# Sheet2.net
KiCad netlist of a schematic drawn in Altium Designer
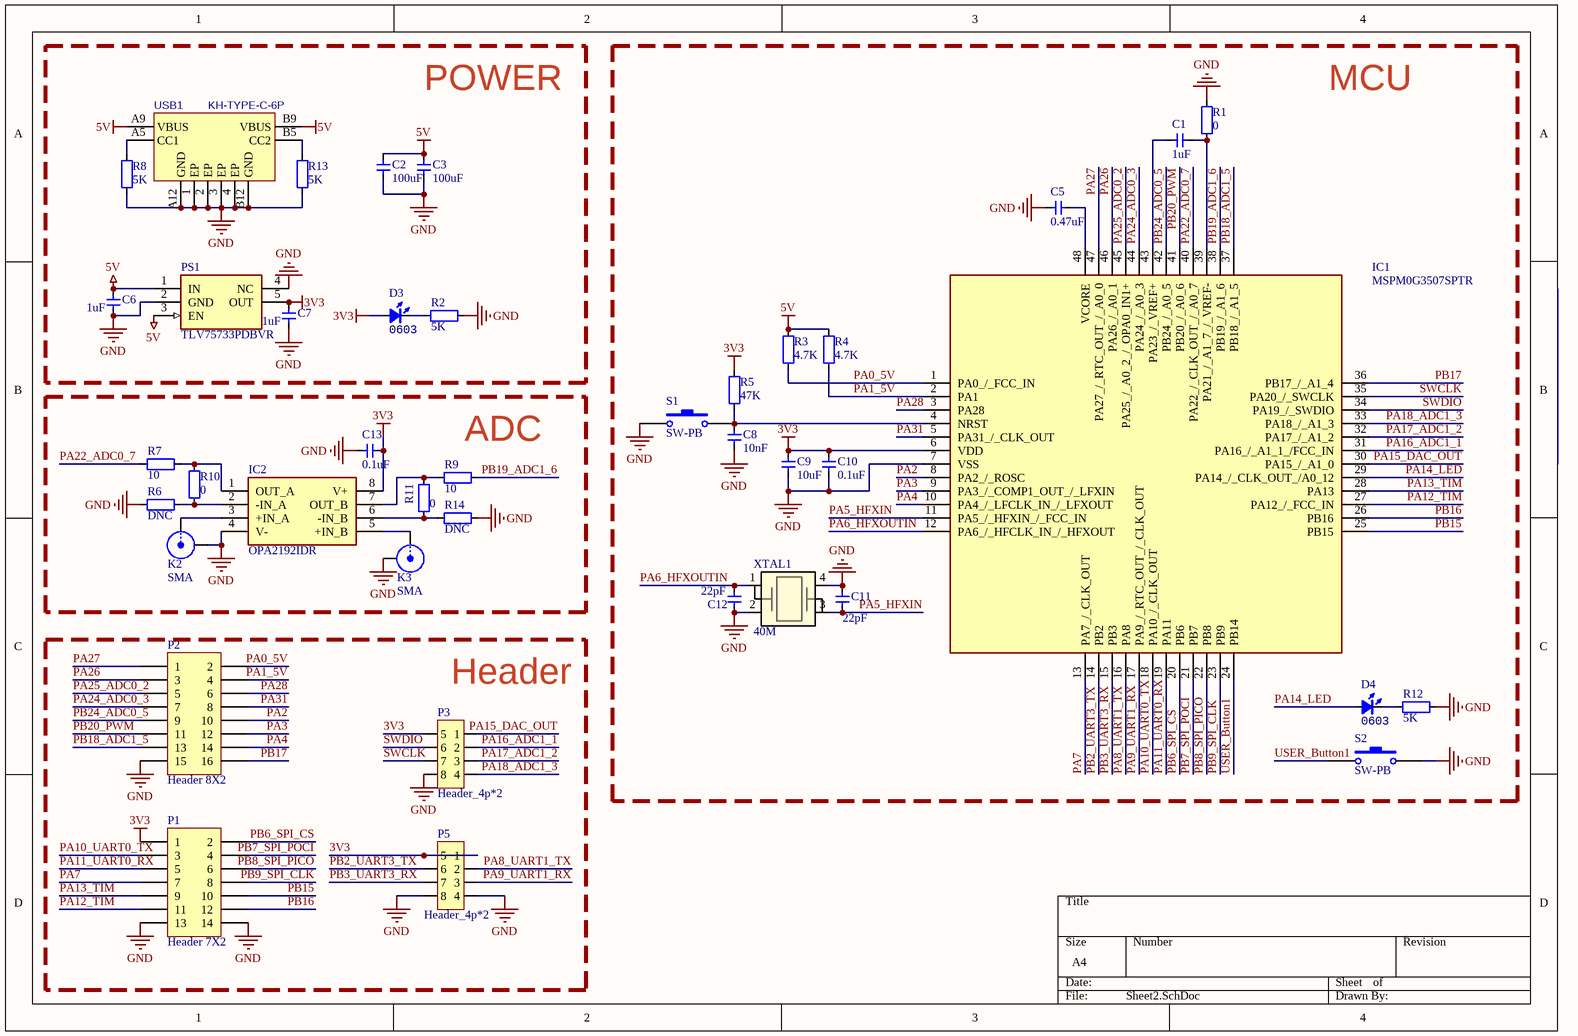
[diagram p0: Sheet2.SchDoc]

(export (version "E")
  (design (tool "Eeschema 10.0.6"))
  (components
    (comp (ref "C1")
      (value "1uF")
      (footprint "CAP_0402")
      (description "Capacitor")
      (libsource (lib "MoonFall") (part "电容-0402"))
    )
    (comp (ref "C2")
      (value "100uF")
      (footprint "1206-CAP")
      (description "Capacitor")
      (libsource (lib "MyPcbLib") (part "电容-1206"))
    )
    (comp (ref "C3")
      (value "100uF")
      (footprint "1206-CAP")
      (description "Capacitor")
      (libsource (lib "MyPcbLib") (part "电容-1206"))
    )
    (comp (ref "C5")
      (value "0.47uF")
      (footprint "CAP_0402")
      (description "Capacitor")
      (libsource (lib "MoonFall") (part "电容-0402"))
    )
    (comp (ref "C6")
      (value "1uF")
      (footprint "CAP_0402")
      (description "Capacitor")
      (libsource (lib "MoonFall") (part "电容-0402"))
    )
    (comp (ref "C7")
      (value "1uF")
      (footprint "CAP_0402")
      (description "Capacitor")
      (libsource (lib "MoonFall") (part "电容-0402"))
    )
    (comp (ref "C8")
      (value "10nF")
      (footprint "CAP_0402")
      (description "Capacitor")
      (libsource (lib "MyPcbLib") (part "电容-0402"))
    )
    (comp (ref "C9")
      (value "10uF")
      (footprint "CAP_0402")
      (description "Capacitor")
      (libsource (lib "MoonFall") (part "电容-0402"))
    )
    (comp (ref "C10")
      (value "0.1uF")
      (footprint "CAP_0402")
      (description "Capacitor")
      (libsource (lib "MoonFall") (part "电容-0402"))
    )
    (comp (ref "C11")
      (value "22pF")
      (footprint "CAP_0402")
      (description "Capacitor")
      (libsource (lib "MoonFall") (part "电容-0402"))
    )
    (comp (ref "C12")
      (value "22pF")
      (footprint "CAP_0402")
      (description "Capacitor")
      (libsource (lib "MoonFall") (part "电容-0402"))
    )
    (comp (ref "C13")
      (value "0.1uF")
      (footprint "CAP_0402")
      (description "Capacitor")
      (libsource (lib "MoonFall") (part "电容-0402"))
    )
    (comp (ref "D3")
      (value "3.3V")
      (footprint "0603_led")
      (description "LED")
      (fields (field (name "TYPE") "0603"))
      (libsource (lib "MoonFall") (part "LED_0603"))
    )
    (comp (ref "D4")
      (value "3.3V")
      (footprint "0603_led")
      (description "LED")
      (fields (field (name "TYPE") "0603"))
      (libsource (lib "MoonFall") (part "LED_0603"))
    )
    (comp (ref "IC1")
      (value "MSPM0G3507SPTR")
      (footprint "QFP50P900X900X160-48N")
      (description "Integrated Circuit")
      (fields (field (name "MANUFACTURER_PART_NUMBER") "MSPM0G3507SDGS28R"))
      (libsource (lib "MoonFall") (part "MSPM0G3507SPTR"))
    )
    (comp (ref "IC2")
      (value "OPA2192IDR")
      (footprint "OPA2192IDR")
      (description "Integrated Circuit")
      (fields (field (name "MANUFACTURER_PART_NUMBER") "OPA2192IDR/BKN"))
      (libsource (lib "MoonFall") (part "OPA2192IDR"))
    )
    (comp (ref "K2") (value "SMA") (footprint "SMA-W") (libsource (lib "MoonFall") (part "SMA")))
    (comp (ref "K3") (value "SMA") (footprint "SMA-W") (libsource (lib "MoonFall") (part "SMA")))
    (comp (ref "P1")
      (value "Header 7X2")
      (footprint "201S2X7")
      (description "Header, 7-Pin, Dual row")
      (fields (field (name "PUBLISHER") "Altium Limited"))
      (libsource (lib "Miscellaneous Connectors") (part "Header 7X2"))
    )
    (comp (ref "P2")
      (value "Header 8X2")
      (footprint "201S2X8")
      (description "Header, 8-Pin, Dual row")
      (fields (field (name "PUBLISHER") "Altium Limited"))
      (libsource (lib "Miscellaneous Connectors") (part "Header 8X2"))
    )
    (comp (ref "P3")
      (value "Header_4p*2")
      (footprint "201R2X4")
      (libsource (lib "MoonFall") (part "Header_4p*2"))
    )
    (comp (ref "P5")
      (value "Header_4p*2")
      (footprint "201S2X4")
      (libsource (lib "MoonFall") (part "Header_4p*2"))
    )
    (comp (ref "PS1")
      (value "TLV75733PDBVR")
      (footprint "SOT95P280X145-5N")
      (description "Power Supply")
      (fields (field (name "MOUSER PART NUMBER") "595-TLV75733PDBVR"))
      (libsource (lib "AD9959") (part "TLV75733PDBVR"))
    )
    (comp (ref "R1")
      (value "0")
      (footprint "RES_0402")
      (description "Resistor")
      (libsource (lib "MyPcbLib") (part "电阻-0402"))
    )
    (comp (ref "R2")
      (value "5K")
      (footprint "RES_0402")
      (description "Resistor")
      (libsource (lib "MyPcbLib") (part "电阻-0402"))
    )
    (comp (ref "R3")
      (value "4.7K")
      (footprint "RES_0402")
      (description "Resistor")
      (libsource (lib "") (part "电阻-0402_1"))
    )
    (comp (ref "R4")
      (value "4.7K")
      (footprint "RES_0402")
      (description "Resistor")
      (libsource (lib "") (part "电阻-0402_1"))
    )
    (comp (ref "R5")
      (value "47K")
      (footprint "RES_0402")
      (description "Resistor")
      (libsource (lib "") (part "电阻-0402_1"))
    )
    (comp (ref "R6")
      (value "DNC")
      (footprint "RES_0402")
      (description "Resistor")
      (libsource (lib "MyPcbLib") (part "电阻-0402"))
    )
    (comp (ref "R7")
      (value "10")
      (footprint "RES_0402")
      (description "Resistor")
      (libsource (lib "") (part "电阻-0402_1"))
    )
    (comp (ref "R8")
      (value "5K")
      (footprint "RES_0402")
      (description "Resistor")
      (libsource (lib "") (part "电阻-0402_2"))
    )
    (comp (ref "R9")
      (value "10")
      (footprint "RES_0402")
      (description "Resistor")
      (libsource (lib "MyPcbLib") (part "电阻-0402"))
    )
    (comp (ref "R10")
      (value "0")
      (footprint "RES_0402")
      (description "Resistor")
      (libsource (lib "") (part "电阻-0402_2"))
    )
    (comp (ref "R11")
      (value "0")
      (footprint "RES_0402")
      (description "Resistor")
      (libsource (lib "MyPcbLib") (part "电阻-0402"))
    )
    (comp (ref "R12")
      (value "5K")
      (footprint "RES_0402")
      (description "Resistor")
      (libsource (lib "MyPcbLib") (part "电阻-0402"))
    )
    (comp (ref "R13")
      (value "5K")
      (footprint "RES_0402")
      (description "Resistor")
      (libsource (lib "") (part "电阻-0402_2"))
    )
    (comp (ref "R14")
      (value "DNC")
      (footprint "RES_0402")
      (description "Resistor")
      (libsource (lib "") (part "电阻-0402_3"))
    )
    (comp (ref "S1")
      (value "SW-PB")
      (footprint "KEY-K2")
      (description "Switch")
      (fields (field (name "PUBLISHER") "Altium Limited"))
      (libsource (lib "Miscellaneous Devices") (part "SW-PB"))
    )
    (comp (ref "S2")
      (value "SW-PB")
      (footprint "KEY-K2")
      (description "Switch")
      (fields (field (name "PUBLISHER") "Altium Limited"))
      (libsource (lib "Miscellaneous Devices") (part "SW-PB"))
    )
    (comp (ref "USB1")
      (value "KH-TYPE-C-6P")
      (footprint "TYPE-C-SMD_TYPE-C-31-M-16")
      (fields (field (name "BOM_SUPPLIER PART") "C709355") (field (name "CONTRIBUTOR") "LCSC"))
      (libsource (lib "MoonFall") (part "TYPE-C-6P"))
    )
    (comp (ref "XTAL1")
      (value "40M")
      (footprint "3225-25M")
      (description "No Description Available")
      (fields
        (field (name "MANUFACTURER_PART_NUMBER") "NX3225GA-16.000M-STD-CRG-2")
        (field (name "COPYRIGHT") "Copyright (C) 2022 Ultra Librarian. All rights reserved.")
      )
      (libsource (lib "3225晶振") (part "NX3225GA-16.000M-STD-CRG-2"))
    )
  )
  (nets
    (net (code "1") (name "/PA0_5V") (class "Default")
      (node (ref "IC1") (pin "1") (pinfunction "PA0_/_FCC_IN_1") (pintype "passive"))
      (node (ref "P2") (pin "2") (pinfunction "2_2") (pintype "passive"))
      (node (ref "R3") (pin "1") (pinfunction "1_1") (pintype "passive"))
    )
    (net (code "2") (name "/PA1_5V") (class "Default")
      (node (ref "IC1") (pin "2") (pinfunction "PA1_2") (pintype "passive"))
      (node (ref "P2") (pin "4") (pinfunction "4_4") (pintype "passive"))
      (node (ref "R4") (pin "1") (pinfunction "1_1") (pintype "passive"))
    )
    (net (code "3") (name "/PA2") (class "Default")
      (node (ref "IC1") (pin "8") (pinfunction "PA2_/_ROSC_8") (pintype "passive"))
      (node (ref "P2") (pin "10") (pinfunction "10_10") (pintype "passive"))
    )
    (net (code "4") (name "/PA3") (class "Default")
      (node (ref "IC1") (pin "9") (pinfunction "PA3_/_COMP1_OUT_/_LFXIN_9") (pintype "passive"))
      (node (ref "P2") (pin "12") (pinfunction "12_12") (pintype "passive"))
    )
    (net (code "5") (name "/PA4") (class "Default")
      (node (ref "IC1") (pin "10") (pinfunction "PA4_/_LFCLK_IN_/_LFXOUT_10") (pintype "passive"))
      (node (ref "P2") (pin "14") (pinfunction "14_14") (pintype "passive"))
    )
    (net (code "6") (name "/PA5_HFXIN") (class "Default")
      (node (ref "C11") (pin "1") (pinfunction "1_1") (pintype "passive"))
      (node (ref "IC1") (pin "11") (pinfunction "PA5_/_HFXIN_/_FCC_IN_11") (pintype "passive"))
      (node (ref "XTAL1") (pin "3") (pinfunction "3_3") (pintype "passive"))
    )
    (net (code "7") (name "/PA6_HFXOUTIN") (class "Default")
      (node (ref "C12") (pin "2") (pinfunction "2_2") (pintype "passive"))
      (node (ref "IC1") (pin "12") (pinfunction "PA6_/_HFCLK_IN_/_HFXOUT_12") (pintype "passive"))
      (node (ref "XTAL1") (pin "1") (pinfunction "1_1") (pintype "passive"))
    )
    (net (code "8") (name "/PA7") (class "Default")
      (node (ref "IC1") (pin "13") (pinfunction "PA7_/_CLK_OUT_13") (pintype "passive"))
      (node (ref "P1") (pin "7") (pinfunction "7_7") (pintype "passive"))
    )
    (net (code "9") (name "/PA8_UART1_TX") (class "Default")
      (node (ref "IC1") (pin "16") (pinfunction "PA8_16") (pintype "passive"))
      (node (ref "P5") (pin "2") (pinfunction "2_2") (pintype "passive"))
    )
    (net (code "10") (name "/PA9_UART1_RX") (class "Default")
      (node (ref "IC1") (pin "17") (pinfunction "PA9_/_RTC_OUT_/_CLK_OUT_17") (pintype "passive"))
      (node (ref "P5") (pin "3") (pinfunction "3_3") (pintype "passive"))
    )
    (net (code "11") (name "/PA10_UART0_TX") (class "Default")
      (node (ref "IC1") (pin "18") (pinfunction "PA10_/_CLK_OUT_18") (pintype "passive"))
      (node (ref "P1") (pin "3") (pinfunction "3_3") (pintype "passive"))
    )
    (net (code "12") (name "/PA11_UART0_RX") (class "Default")
      (node (ref "IC1") (pin "19") (pinfunction "PA11_19") (pintype "passive"))
      (node (ref "P1") (pin "5") (pinfunction "5_5") (pintype "passive"))
    )
    (net (code "13") (name "/PA12_TIM") (class "Default")
      (node (ref "IC1") (pin "27") (pinfunction "PA12_/_FCC_IN_27") (pintype "passive"))
      (node (ref "P1") (pin "11") (pinfunction "11_11") (pintype "passive"))
    )
    (net (code "14") (name "/PA13_TIM") (class "Default")
      (node (ref "IC1") (pin "28") (pinfunction "PA13_28") (pintype "passive"))
      (node (ref "P1") (pin "9") (pinfunction "9_9") (pintype "passive"))
    )
    (net (code "15") (name "/PA14_LED") (class "Default")
      (node (ref "D4") (pin "1") (pinfunction "A_1") (pintype "passive"))
      (node (ref "IC1") (pin "29") (pinfunction "PA14_/_CLK_OUT_/A0_12_29") (pintype "passive"))
    )
    (net (code "16") (name "/PA15_DAC_OUT") (class "Default")
      (node (ref "IC1") (pin "30") (pinfunction "PA15_/_A1_0_30") (pintype "passive"))
      (node (ref "P3") (pin "1") (pinfunction "1_1") (pintype "passive"))
    )
    (net (code "17") (name "/PA16_ADC1_1") (class "Default")
      (node (ref "IC1") (pin "31") (pinfunction "PA16_/_A1_1_/FCC_IN_31") (pintype "passive"))
      (node (ref "P3") (pin "2") (pinfunction "2_2") (pintype "passive"))
    )
    (net (code "18") (name "/PA17_ADC1_2") (class "Default")
      (node (ref "IC1") (pin "32") (pinfunction "PA17_/_A1_2_32") (pintype "passive"))
      (node (ref "P3") (pin "3") (pinfunction "3_3") (pintype "passive"))
    )
    (net (code "19") (name "/PA18_ADC1_3") (class "Default")
      (node (ref "IC1") (pin "33") (pinfunction "PA18_/_A1_3_33") (pintype "passive"))
      (node (ref "P3") (pin "4") (pinfunction "4_4") (pintype "passive"))
    )
    (net (code "20") (name "/PA22_ADC0_7") (class "Default")
      (node (ref "IC1") (pin "40") (pinfunction "PA22_/_CLK_OUT_/_A0_7_40") (pintype "passive"))
      (node (ref "R7") (pin "1") (pinfunction "1_1") (pintype "passive"))
    )
    (net (code "21") (name "/PA24_ADC0_3") (class "Default")
      (node (ref "IC1") (pin "44") (pinfunction "PA24_/_A0_3_44") (pintype "passive"))
      (node (ref "P2") (pin "7") (pinfunction "7_7") (pintype "passive"))
    )
    (net (code "22") (name "/PA25_ADC0_2") (class "Default")
      (node (ref "IC1") (pin "45") (pinfunction "PA25_/_A0_2_/_OPA0_IN1+_45") (pintype "passive"))
      (node (ref "P2") (pin "5") (pinfunction "5_5") (pintype "passive"))
    )
    (net (code "23") (name "/PA26") (class "Default")
      (node (ref "IC1") (pin "46") (pinfunction "PA26_/_A0_1_46") (pintype "passive"))
      (node (ref "P2") (pin "3") (pinfunction "3_3") (pintype "passive"))
    )
    (net (code "24") (name "/PA27") (class "Default")
      (node (ref "IC1") (pin "47") (pinfunction "PA27_/_RTC_OUT_/_A0_0_47") (pintype "passive"))
      (node (ref "P2") (pin "1") (pinfunction "1_1") (pintype "passive"))
    )
    (net (code "25") (name "/PA28") (class "Default")
      (node (ref "IC1") (pin "3") (pinfunction "PA28_3") (pintype "passive"))
      (node (ref "P2") (pin "6") (pinfunction "6_6") (pintype "passive"))
    )
    (net (code "26") (name "/PA31") (class "Default")
      (node (ref "IC1") (pin "5") (pinfunction "PA31_/_CLK_OUT_5") (pintype "passive"))
      (node (ref "P2") (pin "8") (pinfunction "8_8") (pintype "passive"))
    )
    (net (code "27") (name "/PB2_UART3_TX") (class "Default")
      (node (ref "IC1") (pin "14") (pinfunction "PB2_14") (pintype "passive"))
      (node (ref "P5") (pin "6") (pinfunction "6_6") (pintype "passive"))
    )
    (net (code "28") (name "/PB3_UART3_RX") (class "Default")
      (node (ref "IC1") (pin "15") (pinfunction "PB3_15") (pintype "passive"))
      (node (ref "P5") (pin "7") (pinfunction "7_7") (pintype "passive"))
    )
    (net (code "29") (name "/PB6_SPI_CS") (class "Default")
      (node (ref "IC1") (pin "20") (pinfunction "PB6_20") (pintype "passive"))
      (node (ref "P1") (pin "2") (pinfunction "2_2") (pintype "passive"))
    )
    (net (code "30") (name "/PB7_SPI_POCI") (class "Default")
      (node (ref "IC1") (pin "21") (pinfunction "PB7_21") (pintype "passive"))
      (node (ref "P1") (pin "4") (pinfunction "4_4") (pintype "passive"))
    )
    (net (code "31") (name "/PB8_SPI_PICO") (class "Default")
      (node (ref "IC1") (pin "22") (pinfunction "PB8_22") (pintype "passive"))
      (node (ref "P1") (pin "6") (pinfunction "6_6") (pintype "passive"))
    )
    (net (code "32") (name "/PB9_SPI_CLK") (class "Default")
      (node (ref "IC1") (pin "23") (pinfunction "PB9_23") (pintype "passive"))
      (node (ref "P1") (pin "8") (pinfunction "8_8") (pintype "passive"))
    )
    (net (code "33") (name "/PB15") (class "Default")
      (node (ref "IC1") (pin "25") (pinfunction "PB15_25") (pintype "passive"))
      (node (ref "P1") (pin "10") (pinfunction "10_10") (pintype "passive"))
    )
    (net (code "34") (name "/PB16") (class "Default")
      (node (ref "IC1") (pin "26") (pinfunction "PB16_26") (pintype "passive"))
      (node (ref "P1") (pin "12") (pinfunction "12_12") (pintype "passive"))
    )
    (net (code "35") (name "/PB17") (class "Default")
      (node (ref "IC1") (pin "36") (pinfunction "PB17_/_A1_4_36") (pintype "passive"))
      (node (ref "P2") (pin "16") (pinfunction "16_16") (pintype "passive"))
    )
    (net (code "36") (name "/PB18_ADC1_5") (class "Default")
      (node (ref "IC1") (pin "37") (pinfunction "PB18_/_A1_5_37") (pintype "passive"))
      (node (ref "P2") (pin "13") (pinfunction "13_13") (pintype "passive"))
    )
    (net (code "37") (name "/PB19_ADC1_6") (class "Default")
      (node (ref "IC1") (pin "38") (pinfunction "PB19_/_A1_6_38") (pintype "passive"))
      (node (ref "R9") (pin "1") (pinfunction "1_1") (pintype "passive"))
    )
    (net (code "38") (name "/PB20_PWM") (class "Default")
      (node (ref "IC1") (pin "41") (pinfunction "PB20_/_A0_6_41") (pintype "passive"))
      (node (ref "P2") (pin "11") (pinfunction "11_11") (pintype "passive"))
    )
    (net (code "39") (name "/PB24_ADC0_5") (class "Default")
      (node (ref "IC1") (pin "42") (pinfunction "PB24_/_A0_5_42") (pintype "passive"))
      (node (ref "P2") (pin "9") (pinfunction "9_9") (pintype "passive"))
    )
    (net (code "40") (name "/SWCLK") (class "Default")
      (node (ref "IC1") (pin "35") (pinfunction "PA20_/_SWCLK_35") (pintype "passive"))
      (node (ref "P3") (pin "7") (pinfunction "7_7") (pintype "passive"))
    )
    (net (code "41") (name "/SWDIO") (class "Default")
      (node (ref "IC1") (pin "34") (pinfunction "PA19_/_SWDIO_34") (pintype "passive"))
      (node (ref "P3") (pin "6") (pinfunction "6_6") (pintype "passive"))
    )
    (net (code "42") (name "/USER_Button1") (class "Default")
      (node (ref "IC1") (pin "24") (pinfunction "PB14_24") (pintype "passive"))
      (node (ref "S2") (pin "1") (pinfunction "1_1") (pintype "passive"))
    )
    (net (code "43") (name "3V3") (class "Default")
      (node (ref "C10") (pin "2") (pinfunction "2_2") (pintype "passive"))
      (node (ref "C13") (pin "1") (pinfunction "1_1") (pintype "passive"))
      (node (ref "C7") (pin "1") (pinfunction "1_1") (pintype "passive"))
      (node (ref "C9") (pin "2") (pinfunction "2_2") (pintype "passive"))
      (node (ref "D3") (pin "1") (pinfunction "A_1") (pintype "passive"))
      (node (ref "IC1") (pin "6") (pinfunction "VDD_6") (pintype "passive"))
      (node (ref "IC2") (pin "8") (pinfunction "V+_8") (pintype "passive"))
      (node (ref "P1") (pin "1") (pinfunction "1_1") (pintype "passive"))
      (node (ref "P3") (pin "5") (pinfunction "5_5") (pintype "passive"))
      (node (ref "P5") (pin "1") (pinfunction "1_1") (pintype "passive"))
      (node (ref "P5") (pin "5") (pinfunction "5_5") (pintype "passive"))
      (node (ref "PS1") (pin "5") (pinfunction "OUT_5") (pintype "passive"))
      (node (ref "R5") (pin "2") (pinfunction "2_2") (pintype "passive"))
    )
    (net (code "44") (name "5V") (class "Default")
      (node (ref "C2") (pin "2") (pinfunction "2_2") (pintype "passive"))
      (node (ref "C3") (pin "2") (pinfunction "2_2") (pintype "passive"))
      (node (ref "C6") (pin "1") (pinfunction "1_1") (pintype "passive"))
      (node (ref "PS1") (pin "1") (pinfunction "IN_1") (pintype "power_in"))
      (node (ref "PS1") (pin "3") (pinfunction "EN_3") (pintype "input"))
      (node (ref "R3") (pin "2") (pinfunction "2_2") (pintype "passive"))
      (node (ref "R4") (pin "2") (pinfunction "2_2") (pintype "passive"))
      (node (ref "USB1") (pin "A9") (pinfunction "VBUS_A9") (pintype "passive"))
      (node (ref "USB1") (pin "B9") (pinfunction "VBUS_B9") (pintype "passive"))
    )
    (net (code "45") (name "GND") (class "Default")
      (node (ref "C10") (pin "1") (pinfunction "1_1") (pintype "passive"))
      (node (ref "C11") (pin "2") (pinfunction "2_2") (pintype "passive"))
      (node (ref "C12") (pin "1") (pinfunction "1_1") (pintype "passive"))
      (node (ref "C13") (pin "2") (pinfunction "2_2") (pintype "passive"))
      (node (ref "C2") (pin "1") (pinfunction "1_1") (pintype "passive"))
      (node (ref "C3") (pin "1") (pinfunction "1_1") (pintype "passive"))
      (node (ref "C5") (pin "1") (pinfunction "1_1") (pintype "passive"))
      (node (ref "C6") (pin "2") (pinfunction "2_2") (pintype "passive"))
      (node (ref "C7") (pin "2") (pinfunction "2_2") (pintype "passive"))
      (node (ref "C8") (pin "1") (pinfunction "1_1") (pintype "passive"))
      (node (ref "C9") (pin "1") (pinfunction "1_1") (pintype "passive"))
      (node (ref "IC1") (pin "7") (pinfunction "VSS_7") (pintype "passive"))
      (node (ref "IC2") (pin "4") (pinfunction "V-_4") (pintype "passive"))
      (node (ref "K2") (pin "2") (pinfunction "Y_2") (pintype "passive"))
      (node (ref "K3") (pin "2") (pinfunction "Y_2") (pintype "passive"))
      (node (ref "P1") (pin "13") (pinfunction "13_13") (pintype "passive"))
      (node (ref "P1") (pin "14") (pinfunction "14_14") (pintype "passive"))
      (node (ref "P2") (pin "15") (pinfunction "15_15") (pintype "passive"))
      (node (ref "P3") (pin "8") (pinfunction "8_8") (pintype "passive"))
      (node (ref "P5") (pin "4") (pinfunction "4_4") (pintype "passive"))
      (node (ref "P5") (pin "8") (pinfunction "8_8") (pintype "passive"))
      (node (ref "PS1") (pin "2") (pinfunction "GND_2") (pintype "power_in"))
      (node (ref "PS1") (pin "4") (pinfunction "NC_4") (pintype "passive"))
      (node (ref "R1") (pin "1") (pinfunction "1_1") (pintype "passive"))
      (node (ref "R12") (pin "1") (pinfunction "1_1") (pintype "passive"))
      (node (ref "R13") (pin "2") (pinfunction "2_2") (pintype "passive"))
      (node (ref "R14") (pin "2") (pinfunction "2_2") (pintype "passive"))
      (node (ref "R2") (pin "1") (pinfunction "1_1") (pintype "passive"))
      (node (ref "R6") (pin "2") (pinfunction "2_2") (pintype "passive"))
      (node (ref "R8") (pin "2") (pinfunction "2_2") (pintype "passive"))
      (node (ref "S1") (pin "1") (pinfunction "1_1") (pintype "passive"))
      (node (ref "S2") (pin "2") (pinfunction "2_2") (pintype "passive"))
      (node (ref "USB1") (pin "1") (pinfunction "EP_1") (pintype "passive"))
      (node (ref "USB1") (pin "2") (pinfunction "EP_2") (pintype "passive"))
      (node (ref "USB1") (pin "3") (pinfunction "EP_3") (pintype "passive"))
      (node (ref "USB1") (pin "4") (pinfunction "EP_4") (pintype "passive"))
      (node (ref "USB1") (pin "A12") (pinfunction "GND_A12") (pintype "passive"))
      (node (ref "USB1") (pin "B12") (pinfunction "GND_B12") (pintype "passive"))
      (node (ref "XTAL1") (pin "2") (pinfunction "2_2") (pintype "passive"))
      (node (ref "XTAL1") (pin "4") (pinfunction "4_4") (pintype "passive"))
    )
    (net (code "46") (name "Net-(D3-K)") (class "Default")
      (node (ref "D3") (pin "2") (pinfunction "K_2") (pintype "passive"))
      (node (ref "R2") (pin "2") (pinfunction "2_2") (pintype "passive"))
    )
    (net (code "47") (name "Net-(D4-K)") (class "Default")
      (node (ref "D4") (pin "2") (pinfunction "K_2") (pintype "passive"))
      (node (ref "R12") (pin "2") (pinfunction "2_2") (pintype "passive"))
    )
    (net (code "48") (name "Net-(IC1-NRST)") (class "Default")
      (node (ref "C8") (pin "2") (pinfunction "2_2") (pintype "passive"))
      (node (ref "IC1") (pin "4") (pinfunction "NRST_4") (pintype "passive"))
      (node (ref "R5") (pin "1") (pinfunction "1_1") (pintype "passive"))
      (node (ref "S1") (pin "2") (pinfunction "2_2") (pintype "passive"))
    )
    (net (code "49") (name "Net-(IC1-PA21_{slash}_A1_7_{slash}_VREF-)") (class "Default")
      (node (ref "C1") (pin "2") (pinfunction "2_2") (pintype "passive"))
      (node (ref "IC1") (pin "39") (pinfunction "PA21_/_A1_7_/_VREF-_39") (pintype "passive"))
      (node (ref "R1") (pin "2") (pinfunction "2_2") (pintype "passive"))
    )
    (net (code "50") (name "Net-(IC1-PA23_{slash}_VREF+)") (class "Default")
      (node (ref "C1") (pin "1") (pinfunction "1_1") (pintype "passive"))
      (node (ref "IC1") (pin "43") (pinfunction "PA23_/_VREF+_43") (pintype "passive"))
    )
    (net (code "51") (name "Net-(IC1-VCORE)") (class "Default")
      (node (ref "C5") (pin "2") (pinfunction "2_2") (pintype "passive"))
      (node (ref "IC1") (pin "48") (pinfunction "VCORE_48") (pintype "passive"))
    )
    (net (code "52") (name "Net-(IC2-+IN_A)") (class "Default")
      (node (ref "IC2") (pin "3") (pinfunction "+IN_A_3") (pintype "passive"))
      (node (ref "K2") (pin "1") (pinfunction "X_1") (pintype "passive"))
    )
    (net (code "53") (name "Net-(IC2-+IN_B)") (class "Default")
      (node (ref "IC2") (pin "5") (pinfunction "+IN_B_5") (pintype "passive"))
      (node (ref "K3") (pin "1") (pinfunction "X_1") (pintype "passive"))
    )
    (net (code "54") (name "Net-(IC2--IN_A)") (class "Default")
      (node (ref "IC2") (pin "2") (pinfunction "-IN_A_2") (pintype "passive"))
      (node (ref "R10") (pin "2") (pinfunction "2_2") (pintype "passive"))
      (node (ref "R6") (pin "1") (pinfunction "1_1") (pintype "passive"))
    )
    (net (code "55") (name "Net-(IC2--IN_B)") (class "Default")
      (node (ref "IC2") (pin "6") (pinfunction "-IN_B_6") (pintype "passive"))
      (node (ref "R11") (pin "2") (pinfunction "2_2") (pintype "passive"))
      (node (ref "R14") (pin "1") (pinfunction "1_1") (pintype "passive"))
    )
    (net (code "56") (name "Net-(IC2-OUT_A)") (class "Default")
      (node (ref "IC2") (pin "1") (pinfunction "OUT_A_1") (pintype "passive"))
      (node (ref "R10") (pin "1") (pinfunction "1_1") (pintype "passive"))
      (node (ref "R7") (pin "2") (pinfunction "2_2") (pintype "passive"))
    )
    (net (code "57") (name "Net-(IC2-OUT_B)") (class "Default")
      (node (ref "IC2") (pin "7") (pinfunction "OUT_B_7") (pintype "passive"))
      (node (ref "R11") (pin "1") (pinfunction "1_1") (pintype "passive"))
      (node (ref "R9") (pin "2") (pinfunction "2_2") (pintype "passive"))
    )
    (net (code "58") (name "Net-(USB1-CC1)") (class "Default")
      (node (ref "R8") (pin "1") (pinfunction "1_1") (pintype "passive"))
      (node (ref "USB1") (pin "A5") (pinfunction "CC1_A5") (pintype "passive"))
    )
    (net (code "59") (name "Net-(USB1-CC2)") (class "Default")
      (node (ref "R13") (pin "1") (pinfunction "1_1") (pintype "passive"))
      (node (ref "USB1") (pin "B5") (pinfunction "CC2_B5") (pintype "passive"))
    )
  )
)
